# pqc-rev2.net
KiCad netlist of a schematic drawn in EAGLE
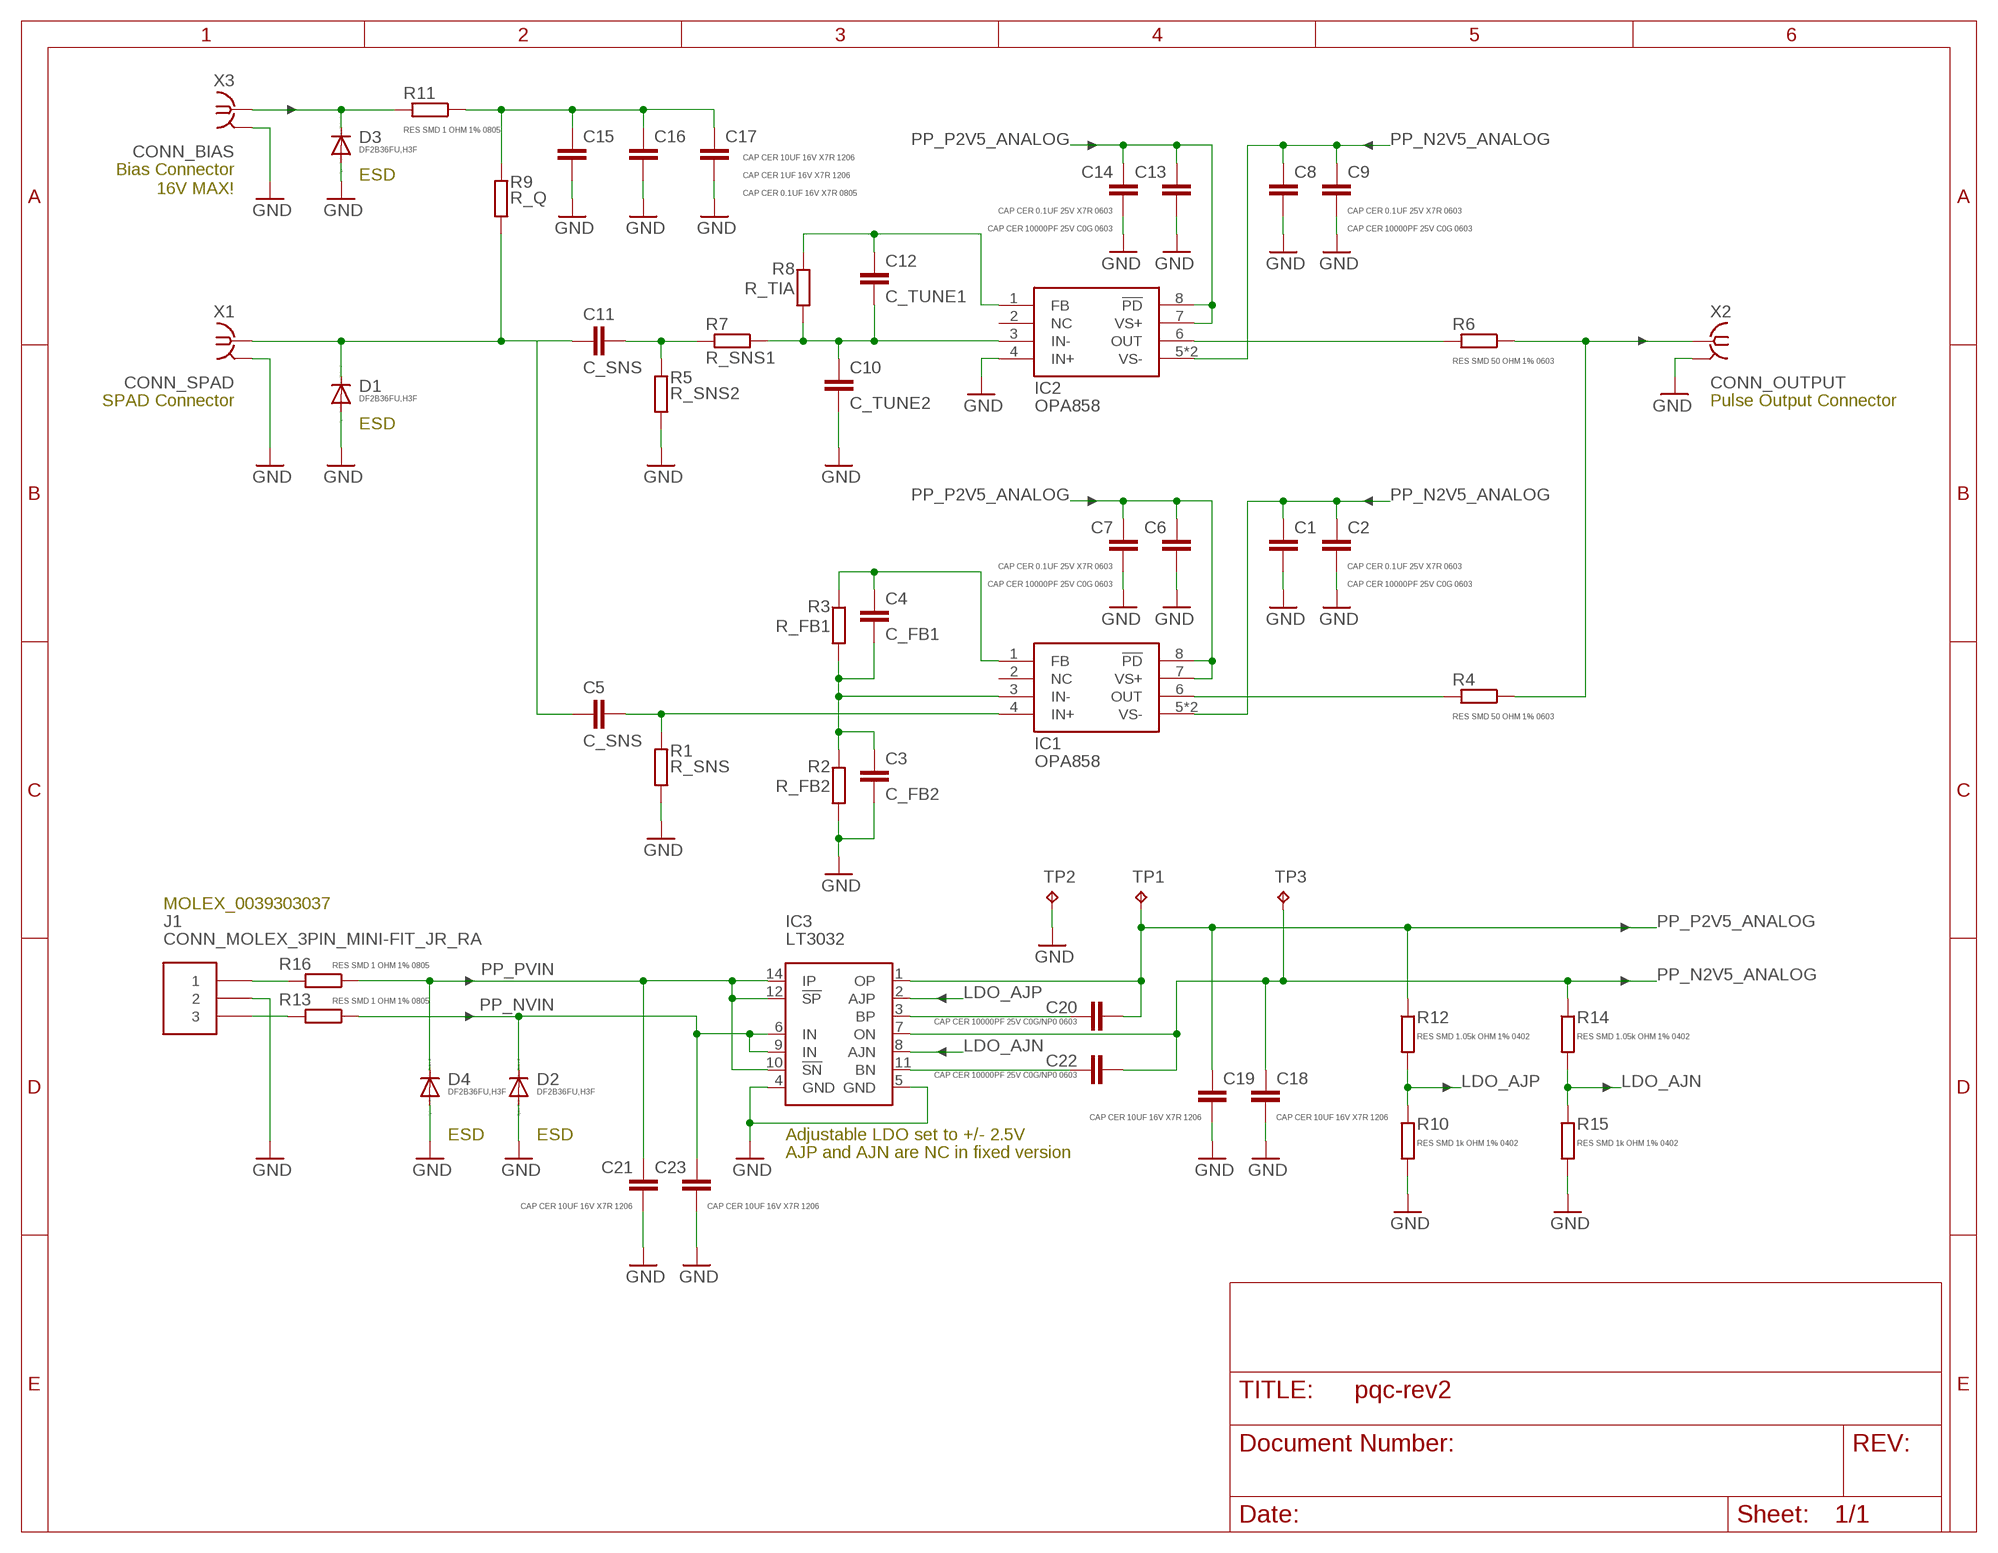
[diagram p0: schematic, sheet 1]

(export (version "E")
  (design (tool "Eeschema 10.0.6"))
  (components
    (comp (ref "C1")
      (value "CAP CER 10000PF 25V C0G 0603")
      (footprint "eagle-import:C0603")
      (libsource (lib "eagle-import") (part "rcl-modified-footprints_C-EUC0603"))
    )
    (comp (ref "C2")
      (value "CAP CER 0.1UF 25V X7R 0603")
      (footprint "eagle-import:C0603")
      (libsource (lib "eagle-import") (part "rcl-modified-footprints_C-EUC0603"))
    )
    (comp (ref "C3")
      (value "C_FB2")
      (footprint "eagle-import:C0402")
      (libsource (lib "eagle-import") (part "rcl-modified-footprints_C-EUC0402"))
    )
    (comp (ref "C4")
      (value "C_FB1")
      (footprint "eagle-import:C0402")
      (libsource (lib "eagle-import") (part "rcl-modified-footprints_C-EUC0402"))
    )
    (comp (ref "C5")
      (value "C_SNS")
      (footprint "eagle-import:C0603")
      (libsource (lib "eagle-import") (part "rcl-modified-footprints_C-EUC0603"))
    )
    (comp (ref "C6")
      (value "CAP CER 10000PF 25V C0G 0603")
      (footprint "eagle-import:C0603")
      (libsource (lib "eagle-import") (part "rcl-modified-footprints_C-EUC0603"))
    )
    (comp (ref "C7")
      (value "CAP CER 0.1UF 25V X7R 0603")
      (footprint "eagle-import:C0603")
      (libsource (lib "eagle-import") (part "rcl-modified-footprints_C-EUC0603"))
    )
    (comp (ref "C8")
      (value "CAP CER 10000PF 25V C0G 0603")
      (footprint "eagle-import:C0603")
      (libsource (lib "eagle-import") (part "rcl-modified-footprints_C-EUC0603"))
    )
    (comp (ref "C9")
      (value "CAP CER 0.1UF 25V X7R 0603")
      (footprint "eagle-import:C0603")
      (libsource (lib "eagle-import") (part "rcl-modified-footprints_C-EUC0603"))
    )
    (comp (ref "C10")
      (value "C_TUNE2")
      (footprint "eagle-import:C0402")
      (libsource (lib "eagle-import") (part "rcl-modified-footprints_C-EUC0402"))
    )
    (comp (ref "C11")
      (value "C_SNS")
      (footprint "eagle-import:C0603")
      (libsource (lib "eagle-import") (part "rcl-modified-footprints_C-EUC0603"))
    )
    (comp (ref "C12")
      (value "C_TUNE1")
      (footprint "eagle-import:C0402")
      (libsource (lib "eagle-import") (part "rcl-modified-footprints_C-EUC0402"))
    )
    (comp (ref "C13")
      (value "CAP CER 10000PF 25V C0G 0603")
      (footprint "eagle-import:C0603")
      (libsource (lib "eagle-import") (part "rcl-modified-footprints_C-EUC0603"))
    )
    (comp (ref "C14")
      (value "CAP CER 0.1UF 25V X7R 0603")
      (footprint "eagle-import:C0603")
      (libsource (lib "eagle-import") (part "rcl-modified-footprints_C-EUC0603"))
    )
    (comp (ref "C15")
      (value "CAP CER 0.1UF 16V X7R 0805")
      (footprint "eagle-import:C0805")
      (libsource (lib "eagle-import") (part "C-EUC0805"))
    )
    (comp (ref "C16")
      (value "CAP CER 1UF 16V X7R 1206")
      (footprint "eagle-import:C1206")
      (libsource (lib "eagle-import") (part "C-EUC1206"))
    )
    (comp (ref "C17")
      (value "CAP CER 10UF 16V X7R 1206")
      (footprint "eagle-import:C1206")
      (libsource (lib "eagle-import") (part "C-EUC1206"))
    )
    (comp (ref "C18")
      (value "CAP CER 10UF 16V X7R 1206")
      (footprint "eagle-import:C1206")
      (libsource (lib "eagle-import") (part "C-EUC1206"))
    )
    (comp (ref "C19")
      (value "CAP CER 10UF 16V X7R 1206")
      (footprint "eagle-import:C1206")
      (libsource (lib "eagle-import") (part "C-EUC1206"))
    )
    (comp (ref "C20")
      (value "CAP CER 10000PF 25V C0G/NP0 0603")
      (footprint "eagle-import:C0603")
      (libsource (lib "eagle-import") (part "C-EUC0603"))
    )
    (comp (ref "C21")
      (value "CAP CER 10UF 16V X7R 1206")
      (footprint "eagle-import:C1206")
      (libsource (lib "eagle-import") (part "C-EUC1206"))
    )
    (comp (ref "C22")
      (value "CAP CER 10000PF 25V C0G/NP0 0603")
      (footprint "eagle-import:C0603")
      (libsource (lib "eagle-import") (part "C-EUC0603"))
    )
    (comp (ref "C23")
      (value "CAP CER 10UF 16V X7R 1206")
      (footprint "eagle-import:C1206")
      (libsource (lib "eagle-import") (part "C-EUC1206"))
    )
    (comp (ref "D1")
      (value "DF2B36FU,H3F")
      (footprint "eagle-import:SOD323-W")
      (libsource (lib "eagle-import") (part "DIODE-SOD323-W"))
    )
    (comp (ref "D2")
      (value "DF2B36FU,H3F")
      (footprint "eagle-import:SOD323-W")
      (libsource (lib "eagle-import") (part "DIODE-SOD323-W"))
    )
    (comp (ref "D3")
      (value "DF2B36FU,H3F")
      (footprint "eagle-import:SOD323-W")
      (libsource (lib "eagle-import") (part "DIODE-SOD323-W"))
    )
    (comp (ref "D4")
      (value "DF2B36FU,H3F")
      (footprint "eagle-import:SOD323-W")
      (libsource (lib "eagle-import") (part "DIODE-SOD323-W"))
    )
    (comp (ref "IC1")
      (value "OPA858")
      (footprint "eagle-import:WSON8")
      (libsource (lib "eagle-import") (part "OPA858"))
    )
    (comp (ref "IC2")
      (value "OPA858")
      (footprint "eagle-import:WSON8")
      (libsource (lib "eagle-import") (part "OPA858"))
    )
    (comp (ref "IC3")
      (value "LT3032")
      (footprint "eagle-import:DFN14-4X3DE")
      (libsource (lib "eagle-import") (part "LT3032"))
    )
    (comp (ref "J1")
      (value "CONN_MOLEX_3PIN_MINI-FIT_JR_RA")
      (footprint "eagle-import:CONN_MOLEX_3PIN_MINI-FIT_JR_RA")
      (libsource (lib "eagle-import") (part "CONN_MOLEX_3PIN_MINI-FIT_JR_RA"))
    )
    (comp (ref "R1")
      (value "R_SNS")
      (footprint "eagle-import:R0402")
      (libsource (lib "eagle-import") (part "R-EU_R0402"))
    )
    (comp (ref "R2")
      (value "R_FB2")
      (footprint "eagle-import:R0402")
      (libsource (lib "eagle-import") (part "R-EU_R0402"))
    )
    (comp (ref "R3")
      (value "R_FB1")
      (footprint "eagle-import:R0402")
      (libsource (lib "eagle-import") (part "R-EU_R0402"))
    )
    (comp (ref "R4")
      (value "RES SMD 50 OHM 1% 0603")
      (footprint "eagle-import:R0603")
      (libsource (lib "eagle-import") (part "R-EU_R0603"))
    )
    (comp (ref "R5")
      (value "R_SNS2")
      (footprint "eagle-import:R0402")
      (libsource (lib "eagle-import") (part "R-EU_R0402"))
    )
    (comp (ref "R6")
      (value "RES SMD 50 OHM 1% 0603")
      (footprint "eagle-import:R0603")
      (libsource (lib "eagle-import") (part "R-EU_R0603"))
    )
    (comp (ref "R7")
      (value "R_SNS1")
      (footprint "eagle-import:R0402")
      (libsource (lib "eagle-import") (part "R-EU_R0402"))
    )
    (comp (ref "R8")
      (value "R_TIA")
      (footprint "eagle-import:R0402")
      (libsource (lib "eagle-import") (part "R-EU_R0402"))
    )
    (comp (ref "R9")
      (value "R_Q")
      (footprint "eagle-import:R0805")
      (libsource (lib "eagle-import") (part "rcl_334_R-EU_R0805"))
    )
    (comp (ref "R10")
      (value "RES SMD 1k OHM 1% 0402")
      (footprint "eagle-import:R0402")
      (libsource (lib "eagle-import") (part "R-EU_R0402"))
    )
    (comp (ref "R11")
      (value "RES SMD 1 OHM 1% 0805")
      (footprint "eagle-import:R0805")
      (libsource (lib "eagle-import") (part "rcl_334_R-EU_R0805"))
    )
    (comp (ref "R12")
      (value "RES SMD 1.05k OHM 1% 0402")
      (footprint "eagle-import:R0402")
      (libsource (lib "eagle-import") (part "R-EU_R0402"))
    )
    (comp (ref "R13")
      (value "RES SMD 1 OHM 1% 0805")
      (footprint "eagle-import:R0805")
      (libsource (lib "eagle-import") (part "R-EU_R0805"))
    )
    (comp (ref "R14")
      (value "RES SMD 1.05k OHM 1% 0402")
      (footprint "eagle-import:R0402")
      (libsource (lib "eagle-import") (part "R-EU_R0402"))
    )
    (comp (ref "R15")
      (value "RES SMD 1k OHM 1% 0402")
      (footprint "eagle-import:R0402")
      (libsource (lib "eagle-import") (part "R-EU_R0402"))
    )
    (comp (ref "R16")
      (value "RES SMD 1 OHM 1% 0805")
      (footprint "eagle-import:R0805")
      (libsource (lib "eagle-import") (part "R-EU_R0805"))
    )
    (comp (ref "TP1")
      (value "P2V5")
      (footprint "eagle-import:TP20R")
      (libsource (lib "eagle-import") (part "TPTP20R"))
    )
    (comp (ref "TP2")
      (value "GND")
      (footprint "eagle-import:TP20R")
      (libsource (lib "eagle-import") (part "TPTP20R"))
    )
    (comp (ref "TP3")
      (value "N2V5")
      (footprint "eagle-import:TP20R")
      (libsource (lib "eagle-import") (part "TPTP20R"))
    )
    (comp (ref "X1")
      (value "CONN_SPAD")
      (footprint "eagle-import:J502-ND-142-0701-881_886")
      (fields (field (name "MF") "JOHNSON COMPONENTS") (field (name "MPN") "142-0701-881"))
      (libsource (lib "eagle-import") (part "SMA-142-0701-881/886"))
    )
    (comp (ref "X2")
      (value "CONN_OUTPUT")
      (footprint "eagle-import:J502-ND-142-0701-881_886")
      (fields (field (name "MF") "JOHNSON COMPONENTS") (field (name "MPN") "142-0701-881"))
      (libsource (lib "eagle-import") (part "SMA-142-0701-881/886"))
    )
    (comp (ref "X3")
      (value "CONN_BIAS")
      (footprint "eagle-import:J502-ND-142-0701-881_886")
      (fields (field (name "MF") "JOHNSON COMPONENTS") (field (name "MPN") "142-0701-881"))
      (libsource (lib "eagle-import") (part "SMA-142-0701-881/886"))
    )
  )
  (nets
    (net (code "1") (name "/LDO_AJN") (class "Default")
      (node (ref "IC3") (pin "8") (pinfunction "AJN_8") (pintype "bidirectional"))
      (node (ref "R14") (pin "2") (pinfunction "2_2") (pintype "passive"))
      (node (ref "R15") (pin "1") (pinfunction "1_1") (pintype "passive"))
    )
    (net (code "2") (name "/LDO_AJP") (class "Default")
      (node (ref "IC3") (pin "2") (pinfunction "AJP_2") (pintype "bidirectional"))
      (node (ref "R10") (pin "1") (pinfunction "1_1") (pintype "passive"))
      (node (ref "R12") (pin "2") (pinfunction "2_2") (pintype "passive"))
    )
    (net (code "3") (name "/PP_N2V5_ANALOG") (class "Default")
      (node (ref "C1") (pin "1") (pinfunction "1_1") (pintype "passive"))
      (node (ref "C18") (pin "1") (pinfunction "1_1") (pintype "passive"))
      (node (ref "C2") (pin "1") (pinfunction "1_1") (pintype "passive"))
      (node (ref "C22") (pin "2") (pinfunction "2_2") (pintype "passive"))
      (node (ref "C8") (pin "1") (pinfunction "1_1") (pintype "passive"))
      (node (ref "C9") (pin "1") (pinfunction "1_1") (pintype "passive"))
      (node (ref "IC1") (pin "5") (pinfunction "VS-_5") (pintype "bidirectional"))
      (node (ref "IC1") (pin "PAD") (pinfunction "VS-_PAD") (pintype "bidirectional"))
      (node (ref "IC2") (pin "5") (pinfunction "VS-_5") (pintype "bidirectional"))
      (node (ref "IC2") (pin "PAD") (pinfunction "VS-_PAD") (pintype "bidirectional"))
      (node (ref "IC3") (pin "7") (pinfunction "ON_7") (pintype "power_in"))
      (node (ref "R14") (pin "1") (pinfunction "1_1") (pintype "passive"))
      (node (ref "TP3") (pin "TP") (pinfunction "TP_TP") (pintype "input"))
    )
    (net (code "4") (name "/PP_NVIN") (class "Default")
      (node (ref "C23") (pin "1") (pinfunction "1_1") (pintype "passive"))
      (node (ref "D2") (pin "C") (pinfunction "C_C") (pintype "passive"))
      (node (ref "IC3") (pin "6") (pinfunction "IN_6") (pintype "power_in"))
      (node (ref "IC3") (pin "9") (pinfunction "IN_9") (pintype "power_in"))
      (node (ref "R13") (pin "1") (pinfunction "1_1") (pintype "passive"))
    )
    (net (code "5") (name "/PP_P2V5_ANALOG") (class "Default")
      (node (ref "C13") (pin "1") (pinfunction "1_1") (pintype "passive"))
      (node (ref "C14") (pin "1") (pinfunction "1_1") (pintype "passive"))
      (node (ref "C19") (pin "1") (pinfunction "1_1") (pintype "passive"))
      (node (ref "C20") (pin "2") (pinfunction "2_2") (pintype "passive"))
      (node (ref "C6") (pin "1") (pinfunction "1_1") (pintype "passive"))
      (node (ref "C7") (pin "1") (pinfunction "1_1") (pintype "passive"))
      (node (ref "IC1") (pin "7") (pinfunction "VS+_7") (pintype "bidirectional"))
      (node (ref "IC1") (pin "8") (pinfunction "~{PD}_8") (pintype "bidirectional"))
      (node (ref "IC2") (pin "7") (pinfunction "VS+_7") (pintype "bidirectional"))
      (node (ref "IC2") (pin "8") (pinfunction "~{PD}_8") (pintype "bidirectional"))
      (node (ref "IC3") (pin "1") (pinfunction "OP_1") (pintype "power_in"))
      (node (ref "R12") (pin "1") (pinfunction "1_1") (pintype "passive"))
      (node (ref "TP1") (pin "TP") (pinfunction "TP_TP") (pintype "input"))
    )
    (net (code "6") (name "/PP_PVIN") (class "Default")
      (node (ref "C21") (pin "1") (pinfunction "1_1") (pintype "passive"))
      (node (ref "D4") (pin "C") (pinfunction "C_C") (pintype "passive"))
      (node (ref "IC3") (pin "10") (pinfunction "~{SN}_10") (pintype "bidirectional"))
      (node (ref "IC3") (pin "12") (pinfunction "~{SP}_12") (pintype "bidirectional"))
      (node (ref "IC3") (pin "14") (pinfunction "IP_14") (pintype "power_in"))
      (node (ref "R16") (pin "1") (pinfunction "1_1") (pintype "passive"))
    )
    (net (code "7") (name "GND") (class "Default")
      (node (ref "C1") (pin "2") (pinfunction "2_2") (pintype "passive"))
      (node (ref "C10") (pin "2") (pinfunction "2_2") (pintype "passive"))
      (node (ref "C13") (pin "2") (pinfunction "2_2") (pintype "passive"))
      (node (ref "C14") (pin "2") (pinfunction "2_2") (pintype "passive"))
      (node (ref "C15") (pin "2") (pinfunction "2_2") (pintype "passive"))
      (node (ref "C16") (pin "2") (pinfunction "2_2") (pintype "passive"))
      (node (ref "C17") (pin "2") (pinfunction "2_2") (pintype "passive"))
      (node (ref "C18") (pin "2") (pinfunction "2_2") (pintype "passive"))
      (node (ref "C19") (pin "2") (pinfunction "2_2") (pintype "passive"))
      (node (ref "C2") (pin "2") (pinfunction "2_2") (pintype "passive"))
      (node (ref "C21") (pin "2") (pinfunction "2_2") (pintype "passive"))
      (node (ref "C23") (pin "2") (pinfunction "2_2") (pintype "passive"))
      (node (ref "C3") (pin "2") (pinfunction "2_2") (pintype "passive"))
      (node (ref "C6") (pin "2") (pinfunction "2_2") (pintype "passive"))
      (node (ref "C7") (pin "2") (pinfunction "2_2") (pintype "passive"))
      (node (ref "C8") (pin "2") (pinfunction "2_2") (pintype "passive"))
      (node (ref "C9") (pin "2") (pinfunction "2_2") (pintype "passive"))
      (node (ref "D1") (pin "A") (pinfunction "A_A") (pintype "passive"))
      (node (ref "D2") (pin "A") (pinfunction "A_A") (pintype "passive"))
      (node (ref "D3") (pin "A") (pinfunction "A_A") (pintype "passive"))
      (node (ref "D4") (pin "A") (pinfunction "A_A") (pintype "passive"))
      (node (ref "IC2") (pin "4") (pinfunction "IN+_4") (pintype "bidirectional"))
      (node (ref "IC3") (pin "4") (pinfunction "GND_4") (pintype "power_in"))
      (node (ref "IC3") (pin "5") (pinfunction "GND_5") (pintype "power_in"))
      (node (ref "J1") (pin "2") (pinfunction "2_2") (pintype "bidirectional"))
      (node (ref "R1") (pin "1") (pinfunction "1_1") (pintype "passive"))
      (node (ref "R10") (pin "2") (pinfunction "2_2") (pintype "passive"))
      (node (ref "R15") (pin "2") (pinfunction "2_2") (pintype "passive"))
      (node (ref "R2") (pin "2") (pinfunction "2_2") (pintype "passive"))
      (node (ref "R5") (pin "1") (pinfunction "1_1") (pintype "passive"))
      (node (ref "TP2") (pin "TP") (pinfunction "TP_TP") (pintype "input"))
      (node (ref "X1") (pin "G@1") (pinfunction "GND_G@1") (pintype "power_in"))
      (node (ref "X2") (pin "G@1") (pinfunction "GND_G@1") (pintype "power_in"))
      (node (ref "X3") (pin "G@1") (pinfunction "GND_G@1") (pintype "power_in"))
    )
    (net (code "8") (name "Net-(C11-Pad1)") (class "Default")
      (node (ref "C11") (pin "1") (pinfunction "1_1") (pintype "passive"))
      (node (ref "C5") (pin "1") (pinfunction "1_1") (pintype "passive"))
      (node (ref "D1") (pin "C") (pinfunction "C_C") (pintype "passive"))
      (node (ref "R9") (pin "1") (pinfunction "1_1") (pintype "passive"))
      (node (ref "X1") (pin "1") (pinfunction "1_1") (pintype "passive"))
    )
    (net (code "9") (name "Net-(C11-Pad2)") (class "Default")
      (node (ref "C11") (pin "2") (pinfunction "2_2") (pintype "passive"))
      (node (ref "R5") (pin "2") (pinfunction "2_2") (pintype "passive"))
      (node (ref "R7") (pin "2") (pinfunction "2_2") (pintype "passive"))
    )
    (net (code "10") (name "Net-(C15-Pad1)") (class "Default")
      (node (ref "C15") (pin "1") (pinfunction "1_1") (pintype "passive"))
      (node (ref "C16") (pin "1") (pinfunction "1_1") (pintype "passive"))
      (node (ref "C17") (pin "1") (pinfunction "1_1") (pintype "passive"))
      (node (ref "R11") (pin "1") (pinfunction "1_1") (pintype "passive"))
      (node (ref "R9") (pin "2") (pinfunction "2_2") (pintype "passive"))
    )
    (net (code "11") (name "Net-(D3-PadC)") (class "Default")
      (node (ref "D3") (pin "C") (pinfunction "C_C") (pintype "passive"))
      (node (ref "R11") (pin "2") (pinfunction "2_2") (pintype "passive"))
      (node (ref "X3") (pin "1") (pinfunction "1_1") (pintype "passive"))
    )
    (net (code "12") (name "Net-(IC1-FB)") (class "Default")
      (node (ref "C4") (pin "1") (pinfunction "1_1") (pintype "passive"))
      (node (ref "IC1") (pin "1") (pinfunction "FB_1") (pintype "bidirectional"))
      (node (ref "R3") (pin "1") (pinfunction "1_1") (pintype "passive"))
    )
    (net (code "13") (name "Net-(IC1-IN+)") (class "Default")
      (node (ref "C5") (pin "2") (pinfunction "2_2") (pintype "passive"))
      (node (ref "IC1") (pin "4") (pinfunction "IN+_4") (pintype "bidirectional"))
      (node (ref "R1") (pin "2") (pinfunction "2_2") (pintype "passive"))
    )
    (net (code "14") (name "Net-(IC1-IN-)") (class "Default")
      (node (ref "C3") (pin "1") (pinfunction "1_1") (pintype "passive"))
      (node (ref "C4") (pin "2") (pinfunction "2_2") (pintype "passive"))
      (node (ref "IC1") (pin "3") (pinfunction "IN-_3") (pintype "bidirectional"))
      (node (ref "R2") (pin "1") (pinfunction "1_1") (pintype "passive"))
      (node (ref "R3") (pin "2") (pinfunction "2_2") (pintype "passive"))
    )
    (net (code "15") (name "Net-(IC1-OUT)") (class "Default")
      (node (ref "IC1") (pin "6") (pinfunction "OUT_6") (pintype "bidirectional"))
      (node (ref "R4") (pin "2") (pinfunction "2_2") (pintype "passive"))
    )
    (net (code "16") (name "Net-(IC2-FB)") (class "Default")
      (node (ref "C12") (pin "1") (pinfunction "1_1") (pintype "passive"))
      (node (ref "IC2") (pin "1") (pinfunction "FB_1") (pintype "bidirectional"))
      (node (ref "R8") (pin "1") (pinfunction "1_1") (pintype "passive"))
    )
    (net (code "17") (name "Net-(IC2-IN-)") (class "Default")
      (node (ref "C10") (pin "1") (pinfunction "1_1") (pintype "passive"))
      (node (ref "C12") (pin "2") (pinfunction "2_2") (pintype "passive"))
      (node (ref "IC2") (pin "3") (pinfunction "IN-_3") (pintype "bidirectional"))
      (node (ref "R7") (pin "1") (pinfunction "1_1") (pintype "passive"))
      (node (ref "R8") (pin "2") (pinfunction "2_2") (pintype "passive"))
    )
    (net (code "18") (name "Net-(IC2-OUT)") (class "Default")
      (node (ref "IC2") (pin "6") (pinfunction "OUT_6") (pintype "bidirectional"))
      (node (ref "R6") (pin "2") (pinfunction "2_2") (pintype "passive"))
    )
    (net (code "19") (name "Net-(IC3-BN)") (class "Default")
      (node (ref "C22") (pin "1") (pinfunction "1_1") (pintype "passive"))
      (node (ref "IC3") (pin "11") (pinfunction "BN_11") (pintype "bidirectional"))
    )
    (net (code "20") (name "Net-(IC3-BP)") (class "Default")
      (node (ref "C20") (pin "1") (pinfunction "1_1") (pintype "passive"))
      (node (ref "IC3") (pin "3") (pinfunction "BP_3") (pintype "bidirectional"))
    )
    (net (code "21") (name "Net-(J1-Pad1)") (class "Default")
      (node (ref "J1") (pin "1") (pinfunction "1_1") (pintype "bidirectional"))
      (node (ref "R16") (pin "2") (pinfunction "2_2") (pintype "passive"))
    )
    (net (code "22") (name "Net-(J1-Pad3)") (class "Default")
      (node (ref "J1") (pin "3") (pinfunction "3_3") (pintype "bidirectional"))
      (node (ref "R13") (pin "2") (pinfunction "2_2") (pintype "passive"))
    )
    (net (code "23") (name "Net-(R4-Pad1)") (class "Default")
      (node (ref "R4") (pin "1") (pinfunction "1_1") (pintype "passive"))
      (node (ref "R6") (pin "1") (pinfunction "1_1") (pintype "passive"))
      (node (ref "X2") (pin "1") (pinfunction "1_1") (pintype "passive"))
    )
    (net (code "24") (name "unconnected-(IC1-NC-Pad2)") (class "Default")
      (node (ref "IC1") (pin "2") (pinfunction "NC_2") (pintype "bidirectional"))
    )
    (net (code "25") (name "unconnected-(IC2-NC-Pad2)") (class "Default")
      (node (ref "IC2") (pin "2") (pinfunction "NC_2") (pintype "bidirectional"))
    )
  )
)
